# SCH_NFC-card_2024-10-09.net
KiCad netlist of a schematic drawn in EasyEDA
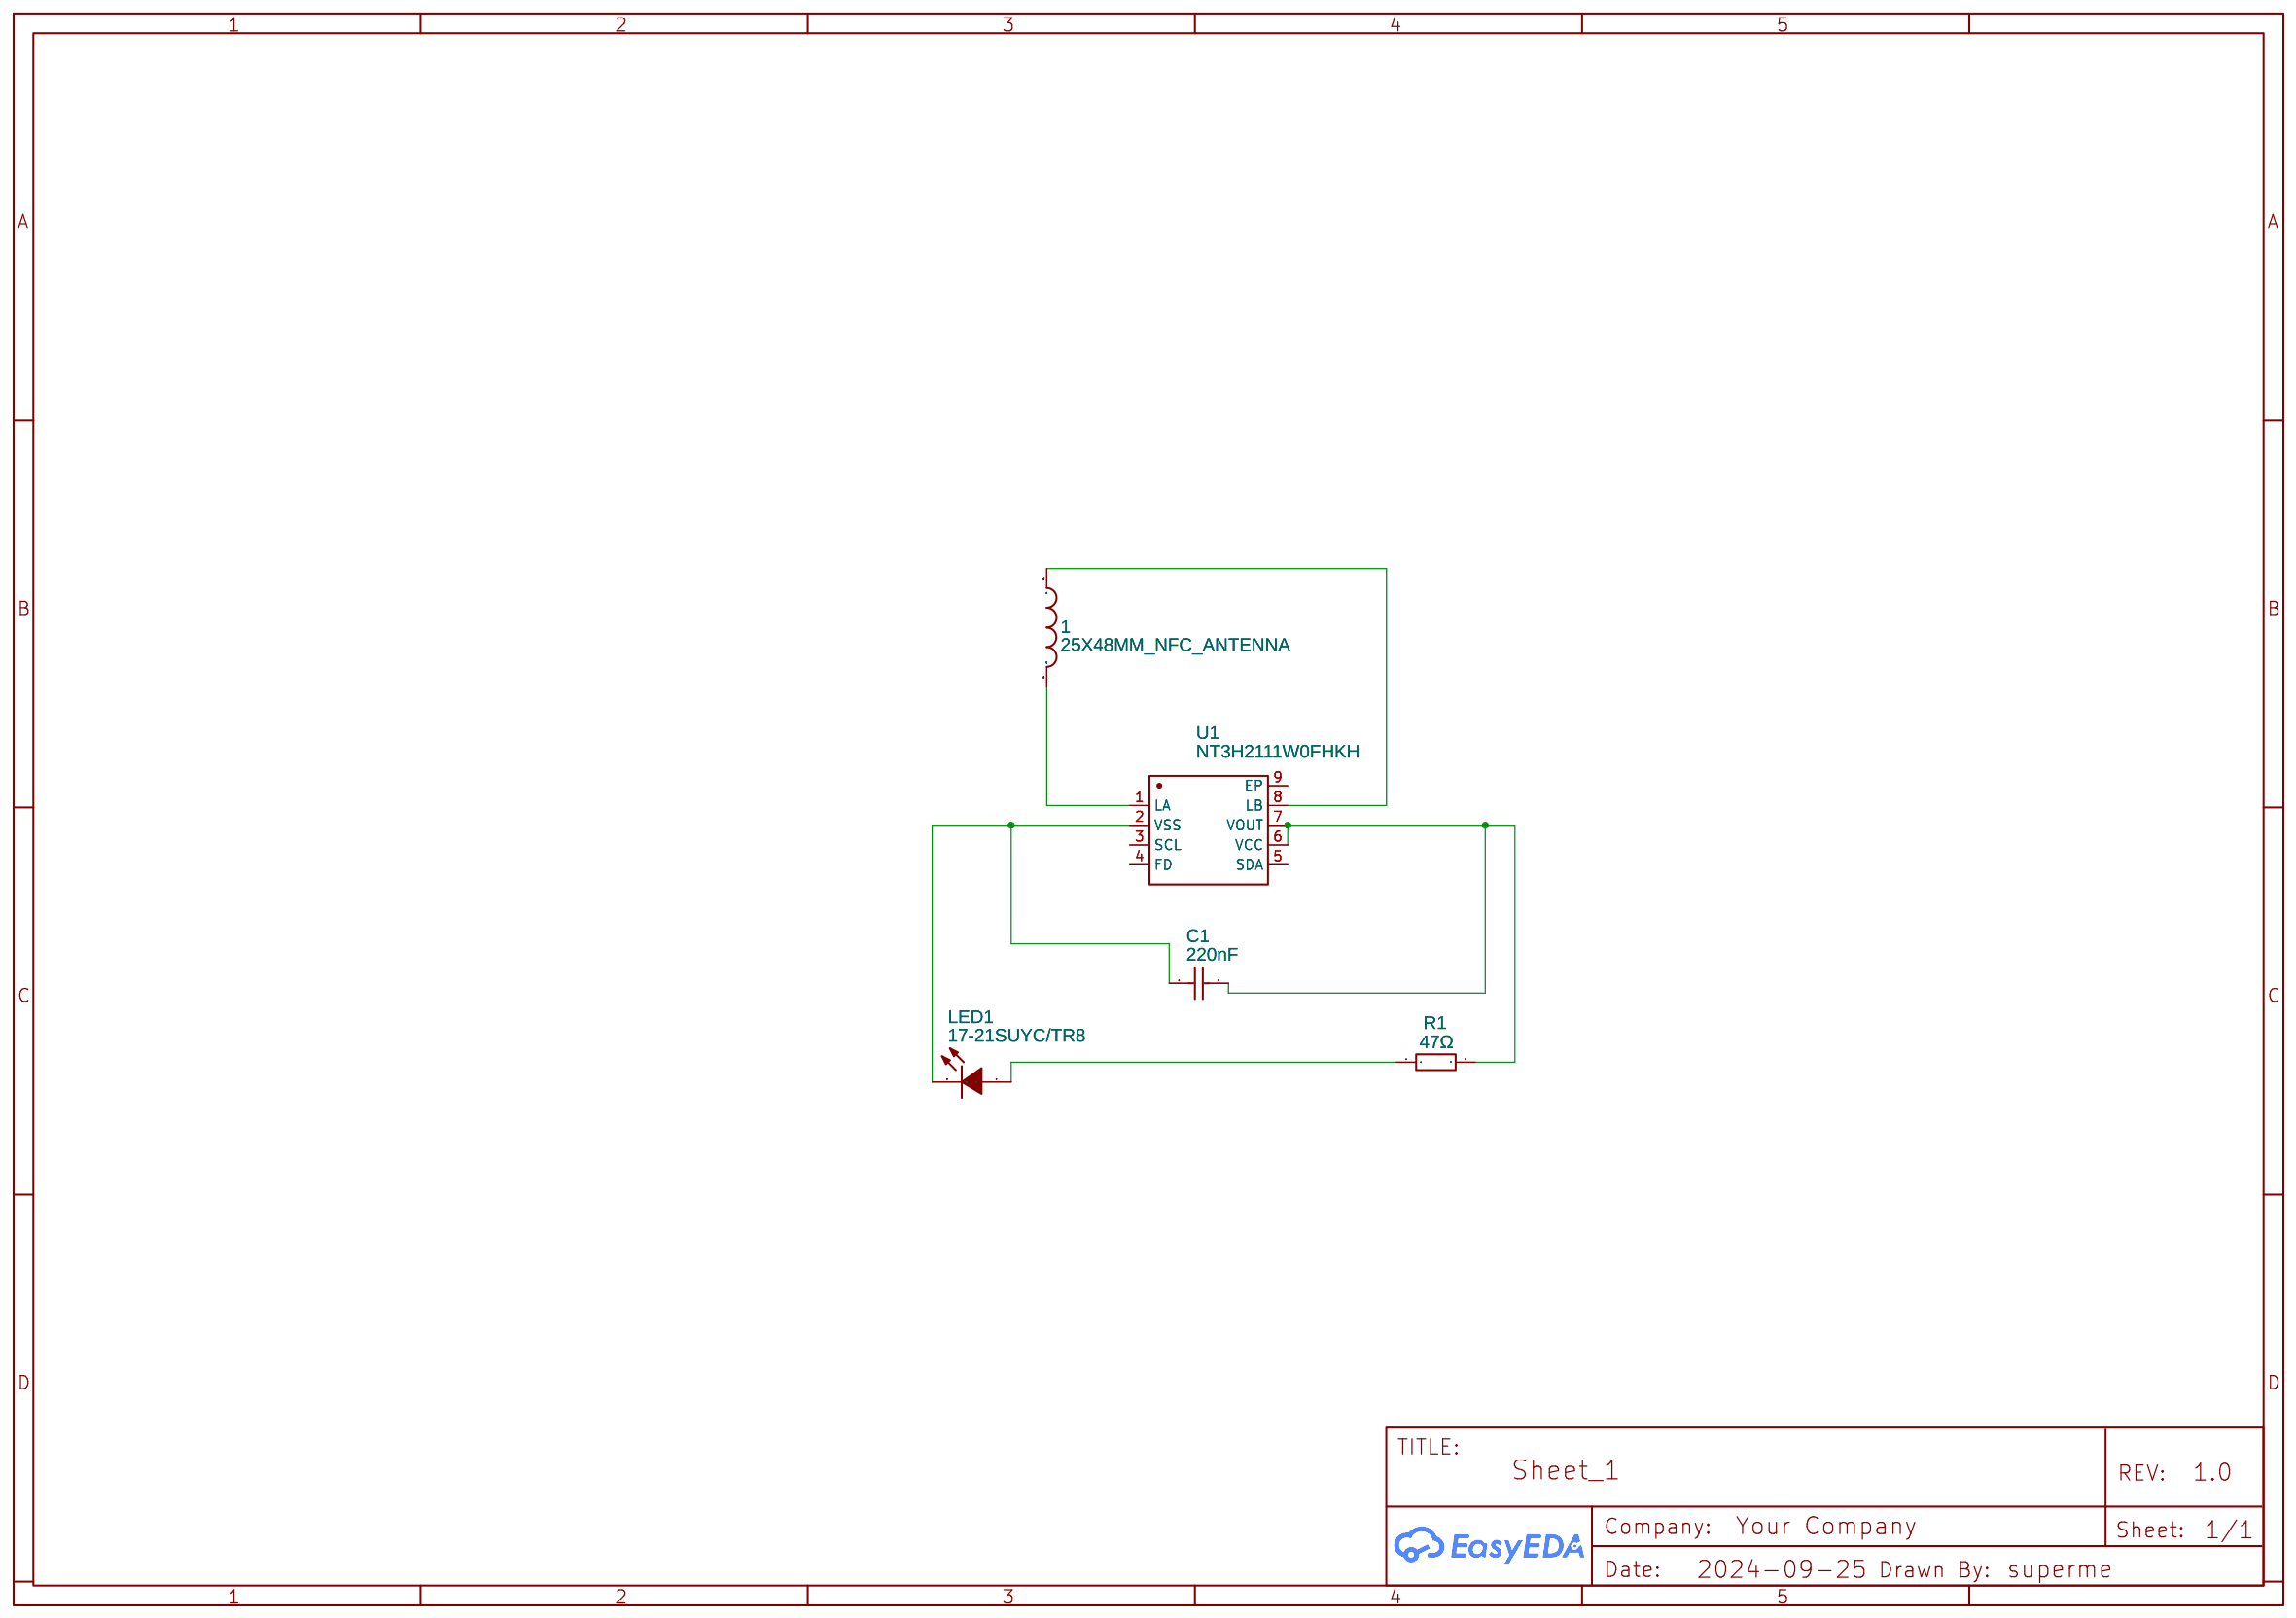
[diagram p0: schematic sheet]

(export (version "E")
  (design (tool "Eeschema 10.0.6"))
  (components
    (comp (ref "1") (value "25X48MM_NFC_ANTENNA") (libsource (lib "") (part "25X48MM_NFC_ANTENNA")))
    (comp (ref "C1")
      (value "220nF")
      (fields
        (field (name "Manufacturer Part") "CL10B224KA8NNNC")
        (field (name "Manufacturer") "SAMSUNG(三星)")
      )
      (libsource (lib "") (part "CL10B224KA8NNNC"))
    )
    (comp (ref "LED1")
      (value "17-21SUYC/TR8")
      (fields (field (name "Manufacturer Part") "KT-0805黄灯") (field (name "Manufacturer") "KENTO"))
      (libsource (lib "") (part "17-21SUYC/TR8"))
    )
    (comp (ref "R1")
      (value "47Ω")
      (fields
        (field (name "Manufacturer Part") "0603WAF470JT5E")
        (field (name "Manufacturer") "UNI-ROYAL(厚声)")
      )
      (libsource (lib "") (part "0603WAF470JT5E"))
    )
    (comp (ref "U1")
      (value "NT3H2111W0FHKH")
      (fields (field (name "Manufacturer") "NXP(恩智浦)"))
      (libsource (lib "") (part "NT3H2111W0FHKH"))
    )
  )
  (nets
    (net (code "1") (name "Net-(LED1-+)") (class "Default")
      (node (ref "LED1") (pin "1") (pinfunction "+_1") (pintype "unspecified"))
      (node (ref "R1") (pin "1") (pinfunction "1_1") (pintype "input"))
    )
    (net (code "2") (name "Net-(LED1--)") (class "Default")
      (node (ref "C1") (pin "1") (pinfunction "1_1") (pintype "input"))
      (node (ref "LED1") (pin "2") (pinfunction "-_2") (pintype "unspecified"))
      (node (ref "U1") (pin "2") (pinfunction "VSS_2") (pintype "unspecified"))
    )
    (net (code "3") (name "Net-(U1-LA)") (class "Default")
      (node (ref "1") (pin "P$2") (pinfunction "P$2_P$2") (pintype "bidirectional"))
      (node (ref "U1") (pin "1") (pinfunction "LA_1") (pintype "unspecified"))
    )
    (net (code "4") (name "Net-(U1-LB)") (class "Default")
      (node (ref "1") (pin "P$1") (pinfunction "P$1_P$1") (pintype "bidirectional"))
      (node (ref "U1") (pin "8") (pinfunction "LB_8") (pintype "unspecified"))
    )
    (net (code "5") (name "Net-(U1-VCC)") (class "Default")
      (node (ref "C1") (pin "2") (pinfunction "2_2") (pintype "input"))
      (node (ref "R1") (pin "2") (pinfunction "2_2") (pintype "input"))
      (node (ref "U1") (pin "6") (pinfunction "VCC_6") (pintype "unspecified"))
      (node (ref "U1") (pin "7") (pinfunction "VOUT_7") (pintype "unspecified"))
    )
    (net (code "6") (name "unconnected-(U1-EP-Pad9)") (class "Default")
      (node (ref "U1") (pin "9") (pinfunction "EP_9") (pintype "unspecified"))
    )
    (net (code "7") (name "unconnected-(U1-FD-Pad4)") (class "Default")
      (node (ref "U1") (pin "4") (pinfunction "FD_4") (pintype "unspecified"))
    )
    (net (code "8") (name "unconnected-(U1-SCL-Pad3)") (class "Default")
      (node (ref "U1") (pin "3") (pinfunction "SCL_3") (pintype "unspecified"))
    )
    (net (code "9") (name "unconnected-(U1-SDA-Pad5)") (class "Default")
      (node (ref "U1") (pin "5") (pinfunction "SDA_5") (pintype "unspecified"))
    )
  )
)
